# Aux_Outputs.net
KiCad netlist of a schematic drawn in Altium Designer
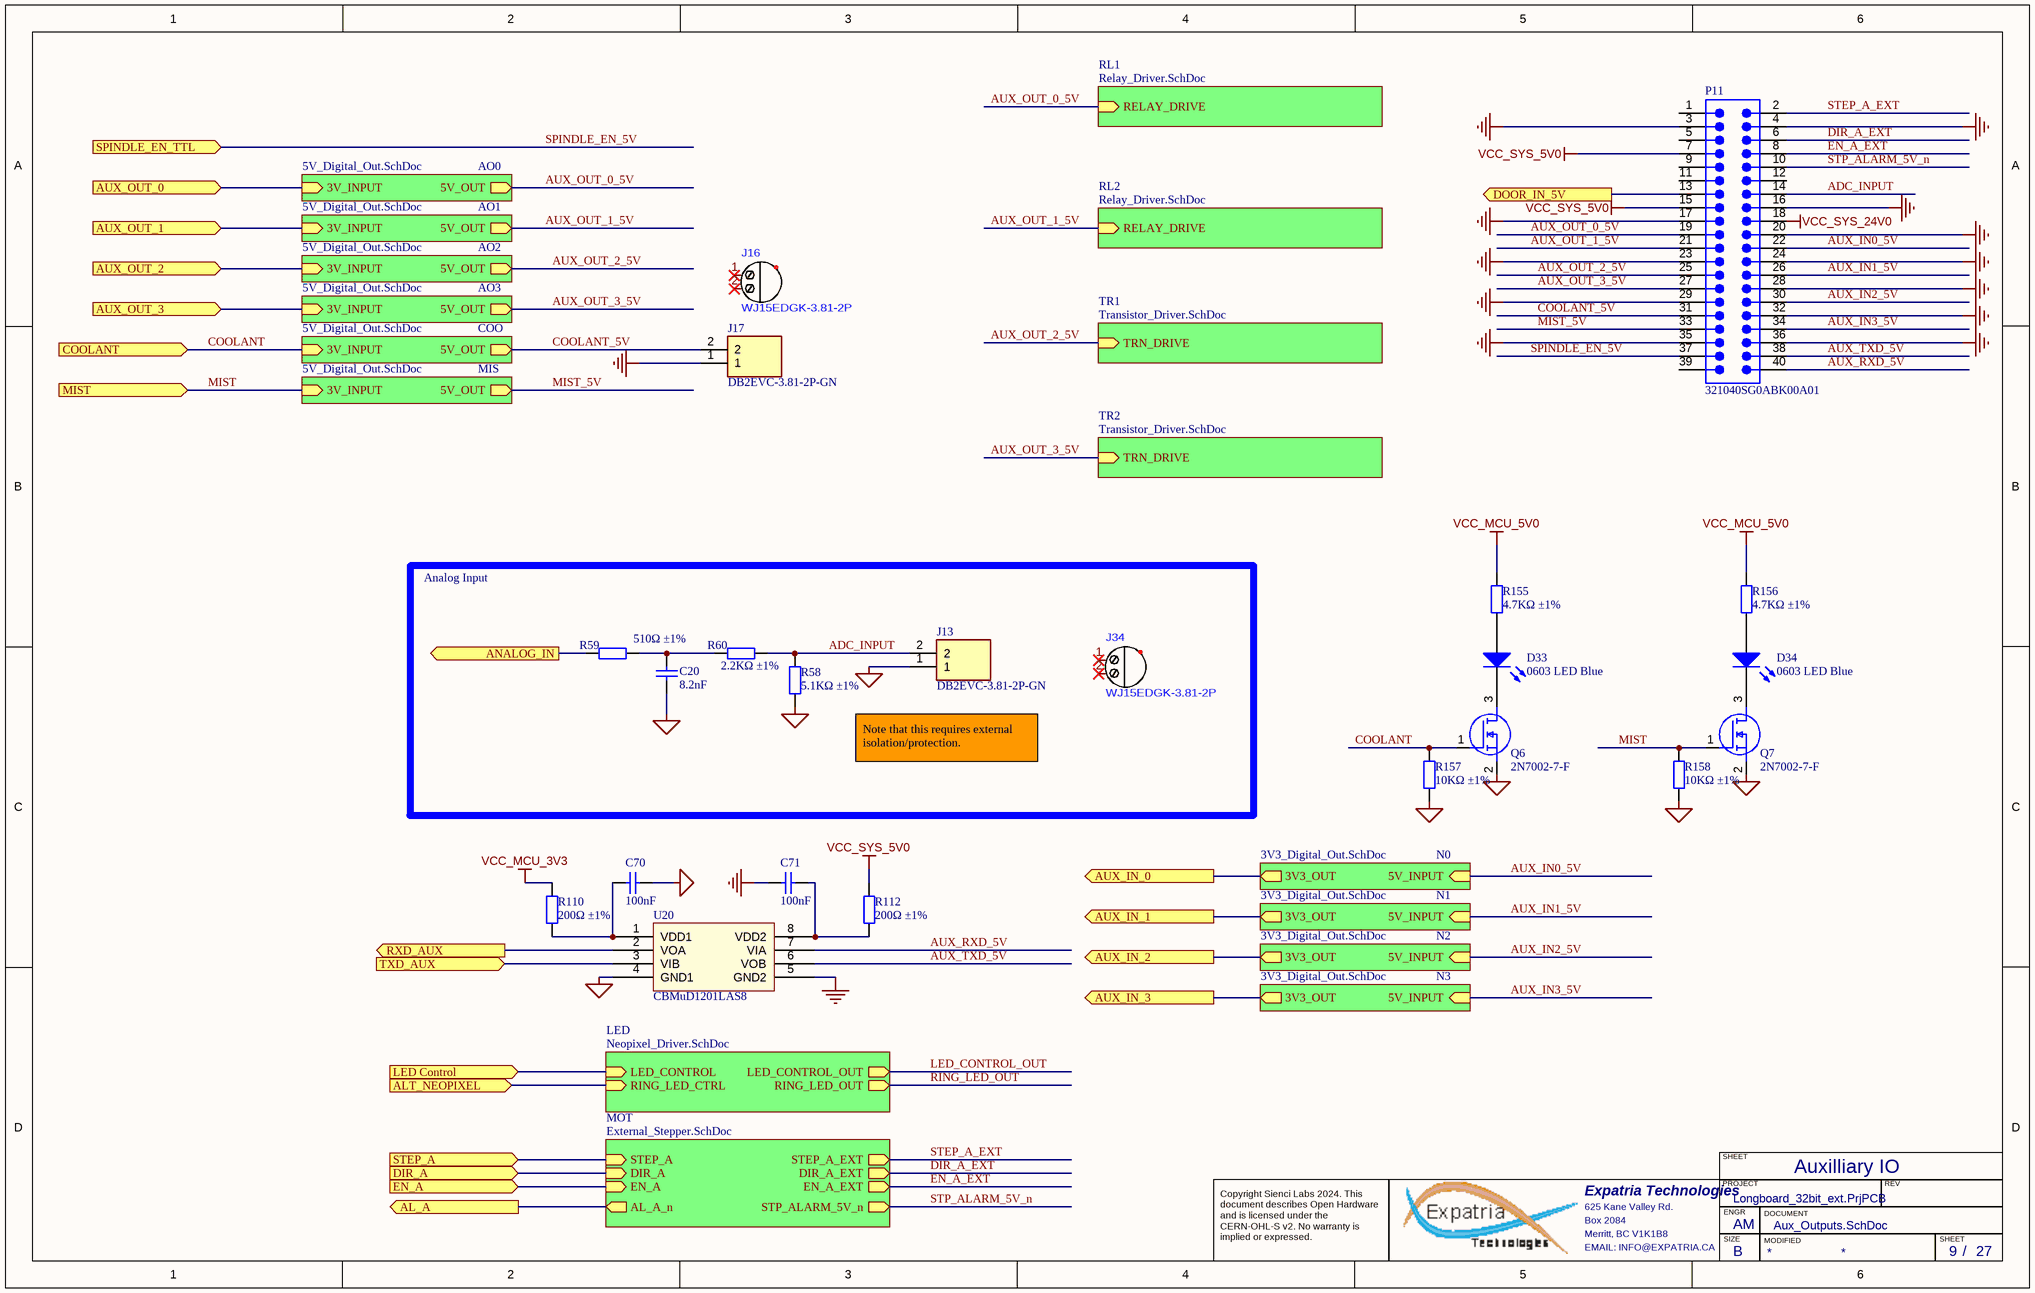
[diagram p0: Aux_Outputs.SchDoc]

(export (version "E")
  (design (tool "Eeschema 10.0.6"))
  (components
    (comp (ref "C20")
      (value "8.2nF")
      (footprint "0603_C")
      (description "50V 8.2nF X7R ±10% 0603 Multilayer Ceramic Capacitors MLCC - SMD/SMT ROHS")
      (fields (field (name "MANUFACTURER") "YAGEO") (field (name "TOLERANCE") "10%"))
      (libsource (lib "Sienci_Labs") (part "0603 8.2nF (822) 10% 50V"))
    )
    (comp (ref "C70")
      (value "100nF")
      (footprint "0402_C")
      (description "16V 100nF X7R ±10% 0402 Multilayer Ceramic Capacitors MLCC - SMD/SMT ROHS")
      (fields (field (name "MANUFACTURER") "Samsung Electro-Mechanics") (field (name "TOLERANCE") "10%"))
      (libsource (lib "Sienci_Labs") (part "0402 100nF (104) 10% 16V"))
    )
    (comp (ref "C71")
      (value "100nF")
      (footprint "0402_C")
      (description "16V 100nF X7R ±10% 0402 Multilayer Ceramic Capacitors MLCC - SMD/SMT ROHS")
      (fields (field (name "MANUFACTURER") "Samsung Electro-Mechanics") (field (name "TOLERANCE") "10%"))
      (libsource (lib "Sienci_Labs") (part "0402 100nF (104) 10% 16V"))
    )
    (comp (ref "D33")
      (value "0603 LED Blue")
      (footprint "0603_LED_S1 - BLUE")
      (description "5mA -40℃~+85℃ Blue 120° 0603 Light Emitting Diodes (LED) ROHS")
      (fields
        (field (name "MANUFACTURER") "TUOZHAN")
        (field (name "MANUFACTURER PART NUMBER") "F.0603.00026/P2-0603B1TS2-06T-001")
      )
      (libsource (lib "Sienci_Labs") (part "0603 LED Blue"))
    )
    (comp (ref "D34")
      (value "0603 LED Blue")
      (footprint "0603_LED_S1 - BLUE")
      (description "5mA -40℃~+85℃ Blue 120° 0603 Light Emitting Diodes (LED) ROHS")
      (fields
        (field (name "MANUFACTURER") "TUOZHAN")
        (field (name "MANUFACTURER PART NUMBER") "F.0603.00026/P2-0603B1TS2-06T-001")
      )
      (libsource (lib "Sienci_Labs") (part "0603 LED Blue"))
    )
    (comp (ref "J13")
      (value "DB2EVC-3.81-2P-GN")
      (footprint "CONN-TH_5P-P3.81_DB2EVC-3.81-2p")
      (description "3.81mm Green Board Edge/Receptacle-Close Push-Pull,P=3.81mm Pluggable System Terminal Block ROHS")
      (fields (field (name "MANUFACTURER") "DIBO"))
      (libsource (lib "Sienci_Labs") (part "DB2EVC-3.81-2P-GN"))
    )
    (comp (ref "J16")
      (value "WJ15EDGK-3.81-2P")
      (description "2 1 3.81mm Green Plug P=3.81mm Pluggable System Terminal Block ROHS")
      (fields (field (name "MANUFACTURER") "Ningbo"))
      (libsource (lib "Sienci_Labs") (part "WJ15EDGK-3.81-2P"))
    )
    (comp (ref "J17")
      (value "DB2EVC-3.81-2P-GN")
      (footprint "CONN-TH_5P-P3.81_DB2EVC-3.81-2p")
      (description "3.81mm Green Board Edge/Receptacle-Close Push-Pull,P=3.81mm Pluggable System Terminal Block ROHS")
      (fields (field (name "MANUFACTURER") "DIBO"))
      (libsource (lib "Sienci_Labs") (part "DB2EVC-3.81-2P-GN"))
    )
    (comp (ref "J34")
      (value "WJ15EDGK-3.81-2P")
      (description "2 1 3.81mm Green Plug P=3.81mm Pluggable System Terminal Block ROHS")
      (fields (field (name "MANUFACTURER") "Ningbo"))
      (libsource (lib "Sienci_Labs") (part "WJ15EDGK-3.81-2P"))
    )
    (comp (ref "P11")
      (value "321040SG0ABK00A01")
      (footprint "IDC-TH_40P-P2.54_321040SG0ABK00A01")
      (description "2.54mm Straight Gold Brass 20 Push - Pull 2.54mm 2 Straight,P=2.54mm IDC Connectors ROHS")
      (fields (field (name "MANUFACTURER") "JILN"))
      (libsource (lib "Sienci_Labs") (part "321040SG0ABK00A01"))
    )
    (comp (ref "Q6")
      (value "2N7002-7-F")
      (footprint "SOT-23(SOT-23-3)")
      (description "60V 115mA 7.5Ω@5V,50mA 370mW N Channel SOT-23 MOSFETs ROHS")
      (fields (field (name "MANUFACTURER") "Diodes Inc.") (field (name "MOUSER PART NUMBER") "621-2N7002-F"))
      (libsource (lib "Sienci_Labs") (part "2N7002-7-F"))
    )
    (comp (ref "Q7")
      (value "2N7002-7-F")
      (footprint "SOT-23(SOT-23-3)")
      (description "60V 115mA 7.5Ω@5V,50mA 370mW N Channel SOT-23 MOSFETs ROHS")
      (fields (field (name "MANUFACTURER") "Diodes Inc.") (field (name "MOUSER PART NUMBER") "621-2N7002-F"))
      (libsource (lib "Sienci_Labs") (part "2N7002-7-F"))
    )
    (comp (ref "R58")
      (value "5.1KΩ ±1%")
      (footprint "0402_R")
      (description "Chip resistor")
      (fields
        (field (name "MANUFACTURER") "Uniroyal Elec")
        (field (name "MANUFACTURER PART NUMBER") "0402WGF5101TCE")
      )
      (libsource (lib "RES") (part "0402 5.1K (5101) 1%"))
    )
    (comp (ref "R59")
      (value "510Ω ±1%")
      (footprint "0402_R")
      (description "Chip resistor")
      (fields
        (field (name "MANUFACTURER") "Uniroyal Elec")
        (field (name "MANUFACTURER PART NUMBER") "0402WGF5100TCE")
      )
      (libsource (lib "Sienci_Labs") (part "0402 510R (5100) 1%"))
    )
    (comp (ref "R60")
      (value "2.2KΩ ±1%")
      (footprint "0402_R")
      (description "Chip resistor")
      (fields
        (field (name "MANUFACTURER") "Uniroyal Elec")
        (field (name "MANUFACTURER PART NUMBER") "0402WGF2201TCE")
      )
      (libsource (lib "RES") (part "0402 2.2K (2201) 1%"))
    )
    (comp (ref "R110")
      (value "200Ω ±1%")
      (footprint "0402_R")
      (description "Chip resistor")
      (fields
        (field (name "MANUFACTURER") "Uniroyal Elec")
        (field (name "MANUFACTURER PART NUMBER") "0402WGF2000TCE")
      )
      (libsource (lib "RES") (part "0402 200R (2000) 1%"))
    )
    (comp (ref "R112")
      (value "200Ω ±1%")
      (footprint "0402_R")
      (description "Chip resistor")
      (fields
        (field (name "MANUFACTURER") "Uniroyal Elec")
        (field (name "MANUFACTURER PART NUMBER") "0402WGF2000TCE")
      )
      (libsource (lib "RES") (part "0402 200R (2000) 1%"))
    )
    (comp (ref "R155")
      (value "4.7KΩ ±1%")
      (footprint "0402_R")
      (description "Chip resistor")
      (fields
        (field (name "MANUFACTURER") "Uniroyal Elec")
        (field (name "MANUFACTURER PART NUMBER") "0402WGF4701TCE")
      )
      (libsource (lib "Sienci_Labs") (part "0402 4.7K (4701) 1%"))
    )
    (comp (ref "R156")
      (value "4.7KΩ ±1%")
      (footprint "0402_R")
      (description "Chip resistor")
      (fields
        (field (name "MANUFACTURER") "Uniroyal Elec")
        (field (name "MANUFACTURER PART NUMBER") "0402WGF4701TCE")
      )
      (libsource (lib "Sienci_Labs") (part "0402 4.7K (4701) 1%"))
    )
    (comp (ref "R157")
      (value "10KΩ ±1%")
      (footprint "0603_R")
      (description "Chip resistor")
      (fields
        (field (name "MANUFACTURER") "Uniroyal Elec")
        (field (name "MANUFACTURER PART NUMBER") "0603WAF1002T5E")
      )
      (libsource (lib "Sienci_Labs") (part "0603 10K (1002) 1%"))
    )
    (comp (ref "R158")
      (value "10KΩ ±1%")
      (footprint "0603_R")
      (description "Chip resistor")
      (fields
        (field (name "MANUFACTURER") "Uniroyal Elec")
        (field (name "MANUFACTURER PART NUMBER") "0603WAF1002T5E")
      )
      (libsource (lib "Sienci_Labs") (part "0603 10K (1002) 1%"))
    )
    (comp (ref "U20")
      (value "CBMuD1201LAS8")
      (footprint "SOIC-8_150mil")
      (description "Dual Channel Isolator")
      (fields (field (name "MANUFACTURER") "Corebai Microelectronics"))
      (libsource (lib "Sienci_Labs") (part "CBMuD1201LAS8"))
    )
  )
  (nets
    (net (code "1") (name "/ADC_INPUT") (class "Default")
      (node (ref "J13") (pin "2") (pinfunction "2_2") (pintype "passive"))
      (node (ref "P11") (pin "14") (pinfunction "14_14") (pintype "passive"))
      (node (ref "R58") (pin "2") (pinfunction "2_2") (pintype "passive"))
      (node (ref "R60") (pin "2") (pinfunction "2_2") (pintype "passive"))
    )
    (net (code "4") (name "/ANALOG_IN") (class "Default")
      (node (ref "R59") (pin "1") (pinfunction "1_1") (pintype "passive"))
    )
    (net (code "5") (name "/AUX_IN0_5V") (class "Default")
      (node (ref "P11") (pin "22") (pinfunction "22_22") (pintype "passive"))
    )
    (net (code "6") (name "/AUX_IN1_5V") (class "Default")
      (node (ref "P11") (pin "26") (pinfunction "26_26") (pintype "passive"))
    )
    (net (code "7") (name "/AUX_IN2_5V") (class "Default")
      (node (ref "P11") (pin "30") (pinfunction "30_30") (pintype "passive"))
    )
    (net (code "8") (name "/AUX_IN3_5V") (class "Default")
      (node (ref "P11") (pin "34") (pinfunction "34_34") (pintype "passive"))
    )
    (net (code "14") (name "/AUX_OUT_0_5V") (class "Default")
      (node (ref "P11") (pin "19") (pinfunction "19_19") (pintype "passive"))
    )
    (net (code "16") (name "/AUX_OUT_1_5V") (class "Default")
      (node (ref "P11") (pin "21") (pinfunction "21_21") (pintype "passive"))
    )
    (net (code "18") (name "/AUX_OUT_2_5V") (class "Default")
      (node (ref "P11") (pin "25") (pinfunction "25_25") (pintype "passive"))
    )
    (net (code "20") (name "/AUX_OUT_3_5V") (class "Default")
      (node (ref "P11") (pin "27") (pinfunction "27_27") (pintype "passive"))
    )
    (net (code "21") (name "/AUX_RXD_5V") (class "Default")
      (node (ref "P11") (pin "40") (pinfunction "40_40") (pintype "passive"))
      (node (ref "U20") (pin "7") (pinfunction "VIA_7") (pintype "passive"))
    )
    (net (code "22") (name "/AUX_TXD_5V") (class "Default")
      (node (ref "P11") (pin "38") (pinfunction "38_38") (pintype "passive"))
      (node (ref "U20") (pin "6") (pinfunction "VOB_6") (pintype "passive"))
    )
    (net (code "23") (name "/COOLANT") (class "Default")
      (node (ref "Q6") (pin "1") (pinfunction "G_1") (pintype "passive"))
      (node (ref "R157") (pin "2") (pinfunction "2_2") (pintype "passive"))
    )
    (net (code "24") (name "/COOLANT_5V") (class "Default")
      (node (ref "J17") (pin "2") (pinfunction "2_2") (pintype "passive"))
      (node (ref "P11") (pin "31") (pinfunction "31_31") (pintype "passive"))
    )
    (net (code "26") (name "/DIR_A_EXT") (class "Default")
      (node (ref "P11") (pin "6") (pinfunction "6_6") (pintype "passive"))
    )
    (net (code "27") (name "/DOOR_IN_5V") (class "Default")
      (node (ref "P11") (pin "13") (pinfunction "13_13") (pintype "passive"))
    )
    (net (code "29") (name "/EN_A_EXT") (class "Default")
      (node (ref "P11") (pin "8") (pinfunction "8_8") (pintype "passive"))
    )
    (net (code "32") (name "/MIST") (class "Default")
      (node (ref "Q7") (pin "1") (pinfunction "G_1") (pintype "passive"))
      (node (ref "R158") (pin "2") (pinfunction "2_2") (pintype "passive"))
    )
    (net (code "33") (name "/MIST_5V") (class "Default")
      (node (ref "P11") (pin "33") (pinfunction "33_33") (pintype "passive"))
    )
    (net (code "35") (name "/RXD_AUX") (class "Default")
      (node (ref "U20") (pin "2") (pinfunction "VOA_2") (pintype "passive"))
    )
    (net (code "36") (name "/SPINDLE_EN_5V") (class "Default")
      (node (ref "P11") (pin "37") (pinfunction "37_37") (pintype "passive"))
    )
    (net (code "38") (name "/STEP_A_EXT") (class "Default")
      (node (ref "P11") (pin "2") (pinfunction "2_2") (pintype "passive"))
    )
    (net (code "39") (name "/STP_ALARM_5V_n") (class "Default")
      (node (ref "P11") (pin "10") (pinfunction "10_10") (pintype "passive"))
    )
    (net (code "40") (name "/TXD_AUX") (class "Default")
      (node (ref "U20") (pin "3") (pinfunction "VIB_3") (pintype "passive"))
    )
    (net (code "41") (name "GND") (class "Default")
      (node (ref "C71") (pin "1") (pinfunction "1_1") (pintype "passive"))
      (node (ref "J17") (pin "1") (pinfunction "1_1") (pintype "passive"))
      (node (ref "P11") (pin "16") (pinfunction "16_16") (pintype "passive"))
      (node (ref "P11") (pin "17") (pinfunction "17_17") (pintype "passive"))
      (node (ref "P11") (pin "20") (pinfunction "20_20") (pintype "passive"))
      (node (ref "P11") (pin "23") (pinfunction "23_23") (pintype "passive"))
      (node (ref "P11") (pin "24") (pinfunction "24_24") (pintype "passive"))
      (node (ref "P11") (pin "28") (pinfunction "28_28") (pintype "passive"))
      (node (ref "P11") (pin "29") (pinfunction "29_29") (pintype "passive"))
      (node (ref "P11") (pin "3") (pinfunction "3_3") (pintype "passive"))
      (node (ref "P11") (pin "32") (pinfunction "32_32") (pintype "passive"))
      (node (ref "P11") (pin "35") (pinfunction "35_35") (pintype "passive"))
      (node (ref "P11") (pin "36") (pinfunction "36_36") (pintype "passive"))
      (node (ref "P11") (pin "4") (pinfunction "4_4") (pintype "passive"))
      (node (ref "U20") (pin "5") (pinfunction "GND2_5") (pintype "passive"))
    )
    (net (code "42") (name "MCU_GND") (class "Default")
      (node (ref "C20") (pin "1") (pinfunction "1_1") (pintype "passive"))
      (node (ref "C70") (pin "2") (pinfunction "2_2") (pintype "passive"))
      (node (ref "J13") (pin "1") (pinfunction "1_1") (pintype "passive"))
      (node (ref "Q6") (pin "2") (pinfunction "S_2") (pintype "passive"))
      (node (ref "Q7") (pin "2") (pinfunction "S_2") (pintype "passive"))
      (node (ref "R157") (pin "1") (pinfunction "1_1") (pintype "passive"))
      (node (ref "R158") (pin "1") (pinfunction "1_1") (pintype "passive"))
      (node (ref "R58") (pin "1") (pinfunction "1_1") (pintype "passive"))
      (node (ref "U20") (pin "4") (pinfunction "GND1_4") (pintype "passive"))
    )
    (net (code "43") (name "Net-(C20-Pad2)") (class "Default")
      (node (ref "C20") (pin "2") (pinfunction "2_2") (pintype "passive"))
      (node (ref "R59") (pin "2") (pinfunction "2_2") (pintype "passive"))
      (node (ref "R60") (pin "1") (pinfunction "1_1") (pintype "passive"))
    )
    (net (code "44") (name "Net-(D33-PadA)") (class "Default")
      (node (ref "D33") (pin "A") (pinfunction "A_A") (pintype "passive"))
      (node (ref "R155") (pin "1") (pinfunction "1_1") (pintype "passive"))
    )
    (net (code "45") (name "Net-(D34-PadA)") (class "Default")
      (node (ref "D34") (pin "A") (pinfunction "A_A") (pintype "passive"))
      (node (ref "R156") (pin "1") (pinfunction "1_1") (pintype "passive"))
    )
    (net (code "46") (name "Net-(Q6-D)") (class "Default")
      (node (ref "D33") (pin "K") (pinfunction "K_K") (pintype "passive"))
      (node (ref "Q6") (pin "3") (pinfunction "D_3") (pintype "passive"))
    )
    (net (code "47") (name "Net-(Q7-D)") (class "Default")
      (node (ref "D34") (pin "K") (pinfunction "K_K") (pintype "passive"))
      (node (ref "Q7") (pin "3") (pinfunction "D_3") (pintype "passive"))
    )
    (net (code "48") (name "Net-(U20-VDD1)") (class "Default")
      (node (ref "C70") (pin "1") (pinfunction "1_1") (pintype "passive"))
      (node (ref "R110") (pin "2") (pinfunction "2_2") (pintype "passive"))
      (node (ref "U20") (pin "1") (pinfunction "VDD1_1") (pintype "passive"))
    )
    (net (code "49") (name "Net-(U20-VDD2)") (class "Default")
      (node (ref "C71") (pin "2") (pinfunction "2_2") (pintype "passive"))
      (node (ref "R112") (pin "2") (pinfunction "2_2") (pintype "passive"))
      (node (ref "U20") (pin "8") (pinfunction "VDD2_8") (pintype "passive"))
    )
    (net (code "50") (name "VCC_MCU_3V3") (class "Default")
      (node (ref "R110") (pin "1") (pinfunction "1_1") (pintype "passive"))
    )
    (net (code "51") (name "VCC_MCU_5V0") (class "Default")
      (node (ref "R155") (pin "2") (pinfunction "2_2") (pintype "passive"))
      (node (ref "R156") (pin "2") (pinfunction "2_2") (pintype "passive"))
    )
    (net (code "52") (name "VCC_SYS_5V0") (class "Default")
      (node (ref "P11") (pin "15") (pinfunction "15_15") (pintype "passive"))
      (node (ref "P11") (pin "7") (pinfunction "7_7") (pintype "passive"))
      (node (ref "R112") (pin "1") (pinfunction "1_1") (pintype "passive"))
    )
    (net (code "53") (name "VCC_SYS_24V0") (class "Default")
      (node (ref "P11") (pin "18") (pinfunction "18_18") (pintype "passive"))
    )
    (net (code "54") (name "unconnected-(J16-Pad1)") (class "Default")
      (node (ref "J16") (pin "1") (pinfunction "1_1") (pintype "passive+no_connect"))
    )
    (net (code "55") (name "unconnected-(J16-Pad2)") (class "Default")
      (node (ref "J16") (pin "2") (pinfunction "2_2") (pintype "passive+no_connect"))
    )
    (net (code "56") (name "unconnected-(J34-Pad1)") (class "Default")
      (node (ref "J34") (pin "1") (pinfunction "1_1") (pintype "passive+no_connect"))
    )
    (net (code "57") (name "unconnected-(J34-Pad2)") (class "Default")
      (node (ref "J34") (pin "2") (pinfunction "2_2") (pintype "passive+no_connect"))
    )
    (net (code "58") (name "unconnected-(P11-Pad1)") (class "Default")
      (node (ref "P11") (pin "1") (pinfunction "1_1") (pintype "passive"))
    )
    (net (code "59") (name "unconnected-(P11-Pad5)") (class "Default")
      (node (ref "P11") (pin "5") (pinfunction "5_5") (pintype "passive"))
    )
    (net (code "60") (name "unconnected-(P11-Pad9)") (class "Default")
      (node (ref "P11") (pin "9") (pinfunction "9_9") (pintype "passive"))
    )
    (net (code "61") (name "unconnected-(P11-Pad11)") (class "Default")
      (node (ref "P11") (pin "11") (pinfunction "11_11") (pintype "passive"))
    )
    (net (code "62") (name "unconnected-(P11-Pad12)") (class "Default")
      (node (ref "P11") (pin "12") (pinfunction "12_12") (pintype "passive"))
    )
    (net (code "63") (name "unconnected-(P11-Pad39)") (class "Default")
      (node (ref "P11") (pin "39") (pinfunction "39_39") (pintype "passive"))
    )
  )
)
